# design.net
KiCad netlist of a schematic drawn in Altium Designer
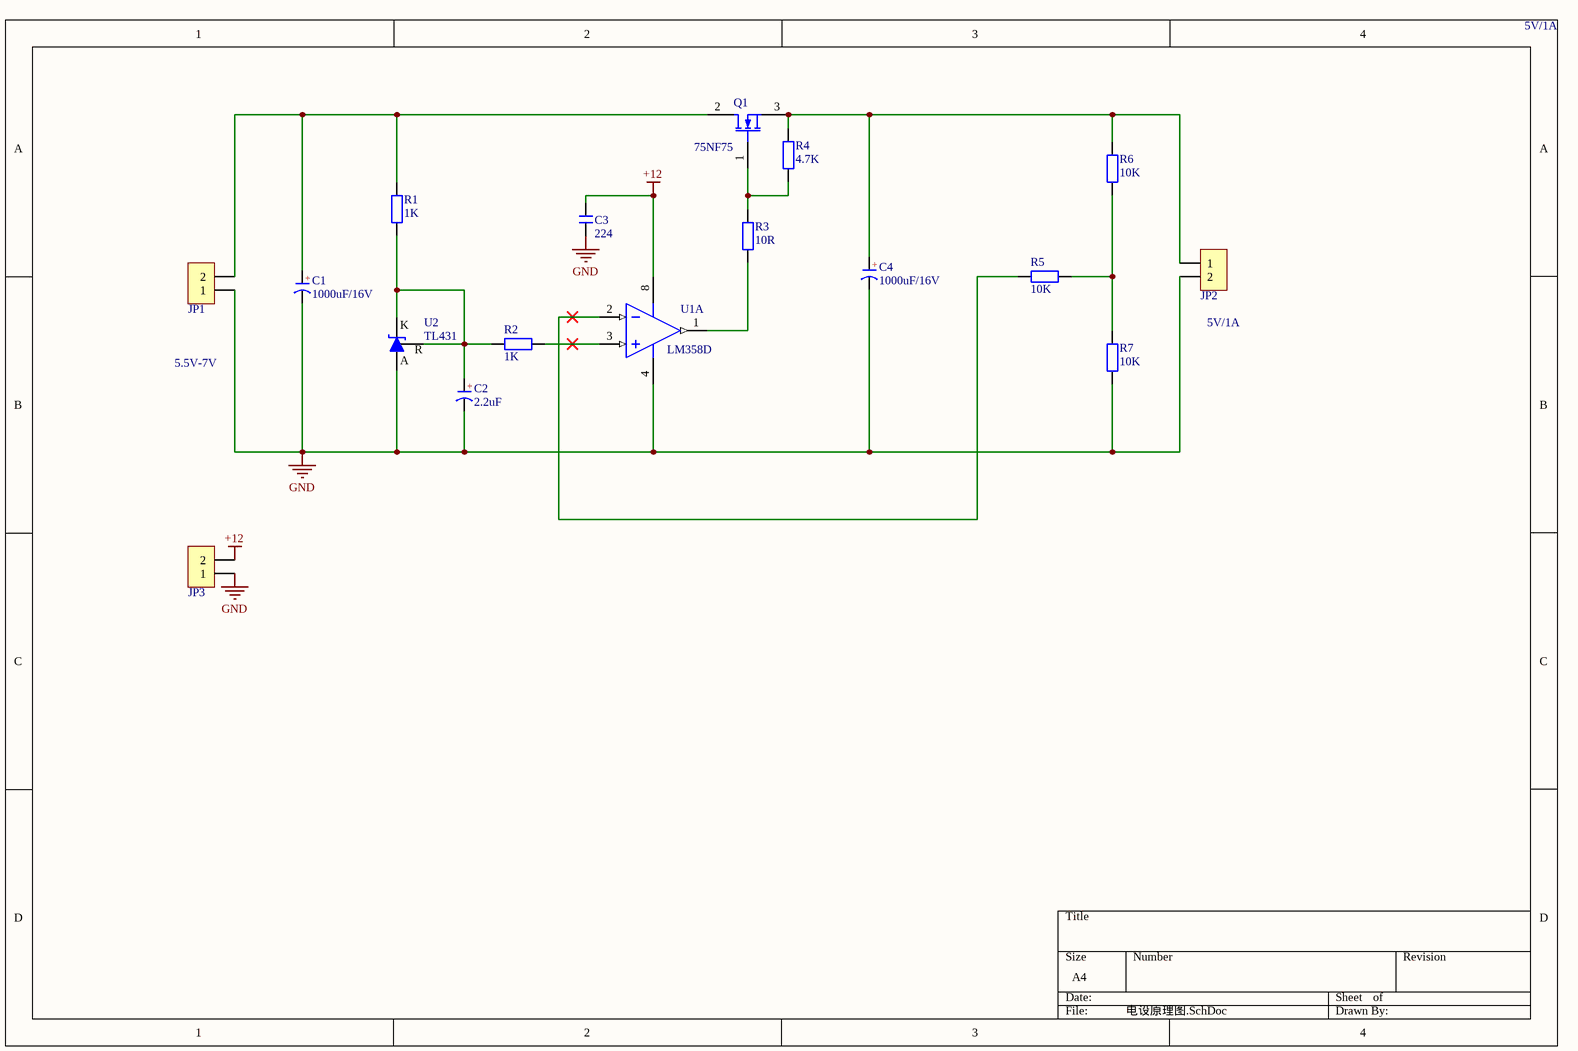
[diagram p0: 电设原理图.SchDoc]

(export (version "E")
  (design (tool "Eeschema 10.0.6"))
  (components
    (comp (ref "C1")
      (value "1000uF/16V")
      (footprint "CS 3.5*8*11.5 - R")
      (description "直插固态电容")
      (libsource (lib "0.1 - 电阻-电容-电感") (part "CS"))
    )
    (comp (ref "C2")
      (value "2.2uF")
      (footprint "CS 2.0*5*8 - C")
      (description "直插固态电容")
      (libsource (lib "0.1 - 电阻-电容-电感") (part "CS"))
    )
    (comp (ref "C3")
      (value "224")
      (footprint "CC 2.2*5")
      (description "独石电容")
      (libsource (lib "0.1 - 电阻-电容-电感") (part "C-MLCC"))
    )
    (comp (ref "C4")
      (value "1000uF/16V")
      (footprint "CS 3.5*8*11.5 - R")
      (description "直插固态电容")
      (libsource (lib "0.1 - 电阻-电容-电感") (part "CS"))
    )
    (comp (ref "JP1")
      (value "HDR-1X2")
      (footprint "KF128-5.08-2P")
      (description "2P接插件")
      (fields (field (name "版权归属") "封装库来自淘宝 ID：黄晶宝石"))
      (libsource (lib "5.4 - 接插件-脚距2.54 (100mil) ") (part "Header 2"))
    )
    (comp (ref "JP2")
      (value "HDR-1X2")
      (footprint "KF128-5.08-2P")
      (description "2P接插件")
      (fields (field (name "版权归属") "封装库来自淘宝 ID：黄晶宝石"))
      (libsource (lib "") (part "Header 2_1"))
    )
    (comp (ref "JP3")
      (value "HDR-1X2")
      (footprint "KF128-5.08-2P")
      (description "2P接插件")
      (fields (field (name "版权归属") "封装库来自淘宝 ID：黄晶宝石"))
      (libsource (lib "5.4 - 接插件-脚距2.54 (100mil) ") (part "Header 2"))
    )
    (comp (ref "Q1")
      (value "75NF75")
      (footprint "TO220A")
      (description "低功耗MOSFET")
      (libsource (lib "0.4 - 三极管-场效应管-可控硅") (part "RUE002N02"))
    )
    (comp (ref "R1")
      (value "1K")
      (footprint "R 0805-HP_M")
      (description "色环电阻")
      (libsource (lib "0.1 - 电阻-电容-电感") (part "R-S"))
    )
    (comp (ref "R2")
      (value "1K")
      (footprint "R 0805-HP_M")
      (description "色环电阻")
      (libsource (lib "0.1 - 电阻-电容-电感") (part "R-S"))
    )
    (comp (ref "R3")
      (value "10R")
      (footprint "R 0805-HP_M")
      (description "色环电阻")
      (libsource (lib "0.1 - 电阻-电容-电感") (part "R-S"))
    )
    (comp (ref "R4")
      (value "4.7K")
      (footprint "R 0805-HP_M")
      (description "色环电阻")
      (libsource (lib "0.1 - 电阻-电容-电感") (part "R-S"))
    )
    (comp (ref "R5")
      (value "10K")
      (footprint "R 0805-HP_M")
      (description "色环电阻")
      (libsource (lib "0.1 - 电阻-电容-电感") (part "R-S"))
    )
    (comp (ref "R6")
      (value "10K")
      (footprint "R 0805-HP_M")
      (description "色环电阻")
      (libsource (lib "0.1 - 电阻-电容-电感") (part "R-S"))
    )
    (comp (ref "R7")
      (value "10K")
      (footprint "R 0805-HP_M")
      (description "色环电阻")
      (libsource (lib "0.1 - 电阻-电容-电感") (part "R-S"))
    )
    (comp (ref "U1")
      (value "LM358D")
      (footprint "DIP-8")
      (description "Fast Settling Dual Operational Amplifier")
      (libsource (lib "OpAmp比较器") (part "LM358_NSC"))
    )
    (comp (ref "U2")
      (value "TL431")
      (footprint "TO92A")
      (description "可调基准稳压芯片")
      (libsource (lib "1.1 - 电源类芯片") (part "TL431-ID"))
    )
  )
  (nets
    (net (code "1") (name "+12") (class "Default")
      (node (ref "C3") (pin "2") (pinfunction "2_2") (pintype "passive"))
      (node (ref "JP3") (pin "2") (pinfunction "2_2") (pintype "passive"))
      (node (ref "U1") (pin "8") (pinfunction "V+_8") (pintype "power_in"))
    )
    (net (code "2") (name "GND") (class "Default")
      (node (ref "C1") (pin "2") (pinfunction "K_2") (pintype "passive"))
      (node (ref "C2") (pin "2") (pinfunction "K_2") (pintype "passive"))
      (node (ref "C3") (pin "1") (pinfunction "1_1") (pintype "passive"))
      (node (ref "C4") (pin "2") (pinfunction "K_2") (pintype "passive"))
      (node (ref "JP1") (pin "1") (pinfunction "1_1") (pintype "passive"))
      (node (ref "JP2") (pin "2") (pinfunction "2_2") (pintype "passive"))
      (node (ref "JP3") (pin "1") (pinfunction "1_1") (pintype "passive"))
      (node (ref "R7") (pin "2") (pinfunction "2_2") (pintype "passive"))
      (node (ref "U1") (pin "4") (pinfunction "V-_4") (pintype "power_in"))
      (node (ref "U2") (pin "2") (pinfunction "A_2") (pintype "passive"))
    )
    (net (code "3") (name "Net-(C1-A)") (class "Default")
      (node (ref "C1") (pin "1") (pinfunction "A_1") (pintype "passive"))
      (node (ref "JP1") (pin "2") (pinfunction "2_2") (pintype "passive"))
      (node (ref "Q1") (pin "2") (pinfunction "2_2") (pintype "passive"))
      (node (ref "R1") (pin "2") (pinfunction "2_2") (pintype "passive"))
    )
    (net (code "4") (name "Net-(C2-A)") (class "Default")
      (node (ref "C2") (pin "1") (pinfunction "A_1") (pintype "passive"))
      (node (ref "R1") (pin "1") (pinfunction "1_1") (pintype "passive"))
      (node (ref "R2") (pin "2") (pinfunction "2_2") (pintype "passive"))
      (node (ref "U2") (pin "1") (pinfunction "R_1") (pintype "passive"))
      (node (ref "U2") (pin "3") (pinfunction "K_3") (pintype "passive"))
    )
    (net (code "5") (name "Net-(C4-A)") (class "Default")
      (node (ref "C4") (pin "1") (pinfunction "A_1") (pintype "passive"))
      (node (ref "JP2") (pin "1") (pinfunction "1_1") (pintype "passive"))
      (node (ref "Q1") (pin "3") (pinfunction "3_3") (pintype "passive"))
      (node (ref "R4") (pin "2") (pinfunction "2_2") (pintype "passive"))
      (node (ref "R6") (pin "1") (pinfunction "1_1") (pintype "passive"))
    )
    (net (code "6") (name "Net-(Q1-Pad1)") (class "Default")
      (node (ref "Q1") (pin "1") (pinfunction "1_1") (pintype "passive"))
      (node (ref "R3") (pin "2") (pinfunction "2_2") (pintype "passive"))
      (node (ref "R4") (pin "1") (pinfunction "1_1") (pintype "passive"))
    )
    (net (code "7") (name "Net-(R5-Pad2)") (class "Default")
      (node (ref "R5") (pin "2") (pinfunction "2_2") (pintype "passive"))
      (node (ref "R6") (pin "2") (pinfunction "2_2") (pintype "passive"))
      (node (ref "R7") (pin "1") (pinfunction "1_1") (pintype "passive"))
    )
    (net (code "8") (name "Net-(U1A-IN1+)") (class "Default")
      (node (ref "R2") (pin "1") (pinfunction "1_1") (pintype "passive"))
      (node (ref "U1") (pin "3") (pinfunction "IN1+_3") (pintype "input"))
    )
    (net (code "9") (name "Net-(U1A-IN1-)") (class "Default")
      (node (ref "R5") (pin "1") (pinfunction "1_1") (pintype "passive"))
      (node (ref "U1") (pin "2") (pinfunction "IN1-_2") (pintype "input"))
    )
    (net (code "10") (name "Net-(U1A-OUT1)") (class "Default")
      (node (ref "R3") (pin "1") (pinfunction "1_1") (pintype "passive"))
      (node (ref "U1") (pin "1") (pinfunction "OUT1_1") (pintype "output"))
    )
  )
)
